# nfc-epd-sensors.net
KiCad netlist of a schematic drawn in Altium Designer
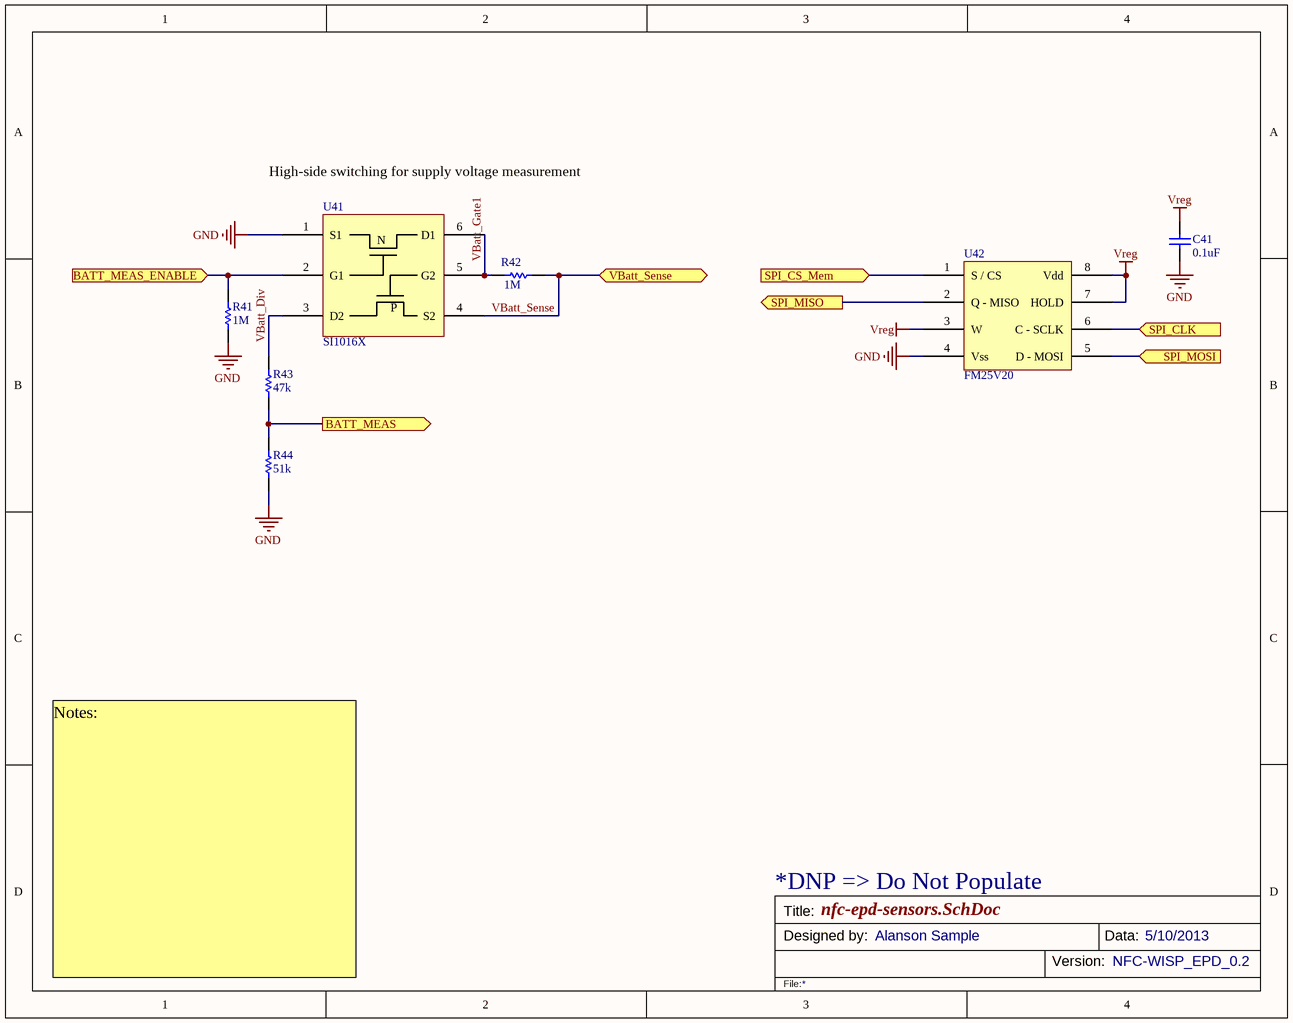
[diagram p0: nfc-epd-sensors.SchDoc]

(export (version "E")
  (design (tool "Eeschema 10.0.6"))
  (components
    (comp (ref "C41")
      (value "0.1uF")
      (footprint "0603")
      (description "Ceramic Capacitor (Surface Mount)")
      (fields (field (name "MANUFACTURER") "Generic Ceramic Chip Cap (TBD)") (field (name "Comment") "Cap"))
      (libsource (lib "WISP_AD10") (part "Cap"))
    )
    (comp (ref "R41")
      (value "1M")
      (footprint "0603")
      (description "Chip Resistor (Surface Mount)")
      (fields (field (name "MANUFACTURER") "Generic Chip Res (TBD)") (field (name "Comment") "Res"))
      (libsource (lib "WISP_AD10") (part "Res"))
    )
    (comp (ref "R42")
      (value "1M")
      (footprint "0603")
      (description "Chip Resistor (Surface Mount)")
      (fields (field (name "MANUFACTURER") "Generic Chip Res (TBD)") (field (name "Comment") "Res"))
      (libsource (lib "WISP_AD10") (part "Res"))
    )
    (comp (ref "R43")
      (value "47k")
      (footprint "0603")
      (description "Chip Resistor (Surface Mount)")
      (fields (field (name "MANUFACTURER") "Generic Chip Res (TBD)") (field (name "Comment") "Res"))
      (libsource (lib "WISP_AD10") (part "Res"))
    )
    (comp (ref "R44")
      (value "51k")
      (footprint "0603")
      (description "Chip Resistor (Surface Mount)")
      (fields (field (name "MANUFACTURER") "Generic Chip Res (TBD)") (field (name "Comment") "Res"))
      (libsource (lib "WISP_AD10") (part "Res"))
    )
    (comp (ref "U41")
      (value "SI1016X")
      (footprint "SC-89-6 Vishay")
      (description "NMOS and PMOS array")
      (fields
        (field (name "MANUFACTURER") "Vishay Siliconix")
        (field (name "MANUFACTURER PART NUMBER") "SI1016X-T1-GE3")
      )
      (libsource (lib "WISP_AD10") (part "SI1016X"))
    )
    (comp (ref "U42")
      (value "FM25V20")
      (footprint "TDFN-8")
      (description "2 Mbit FRAM SPI")
      (fields
        (field (name "DIGI-KEY PART NUMBER") "428-3214-ND")
        (field (name "MANUFACTURER") "Cypress Semiconductor Corp")
      )
      (libsource (lib "WISP_AD10") (part "FM25V20"))
    )
  )
  (nets
    (net (code "1") (name "/BATT_MEAS") (class "Default")
      (node (ref "R43") (pin "1") (pinfunction "1_1") (pintype "passive"))
      (node (ref "R44") (pin "2") (pinfunction "2_2") (pintype "passive"))
    )
    (net (code "2") (name "/BATT_MEAS_ENABLE") (class "Default")
      (node (ref "R41") (pin "2") (pinfunction "2_2") (pintype "passive"))
      (node (ref "U41") (pin "2") (pinfunction "G1_2") (pintype "passive"))
    )
    (net (code "3") (name "/SPI_CLK") (class "Default")
      (node (ref "U42") (pin "6") (pinfunction "C_-_SCLK_6") (pintype "passive"))
    )
    (net (code "4") (name "/SPI_CS_Mem") (class "Default")
      (node (ref "U42") (pin "1") (pinfunction "S_/_CS_1") (pintype "passive"))
    )
    (net (code "5") (name "/SPI_MISO") (class "Default")
      (node (ref "U42") (pin "2") (pinfunction "Q_-_MISO_2") (pintype "passive"))
    )
    (net (code "6") (name "/SPI_MOSI") (class "Default")
      (node (ref "U42") (pin "5") (pinfunction "D_-_MOSI_5") (pintype "passive"))
    )
    (net (code "7") (name "/VBatt_Div") (class "Default")
      (node (ref "R43") (pin "2") (pinfunction "2_2") (pintype "passive"))
      (node (ref "U41") (pin "3") (pinfunction "D2_3") (pintype "passive"))
    )
    (net (code "8") (name "/VBatt_Gate1") (class "Default")
      (node (ref "R42") (pin "2") (pinfunction "2_2") (pintype "passive"))
      (node (ref "U41") (pin "5") (pinfunction "G2_5") (pintype "passive"))
      (node (ref "U41") (pin "6") (pinfunction "D1_6") (pintype "passive"))
    )
    (net (code "9") (name "/VBatt_Sense") (class "Default")
      (node (ref "R42") (pin "1") (pinfunction "1_1") (pintype "passive"))
      (node (ref "U41") (pin "4") (pinfunction "S2_4") (pintype "passive"))
    )
    (net (code "10") (name "GND") (class "Default")
      (node (ref "C41") (pin "1") (pinfunction "1_1") (pintype "passive"))
      (node (ref "R41") (pin "1") (pinfunction "1_1") (pintype "passive"))
      (node (ref "R44") (pin "1") (pinfunction "1_1") (pintype "passive"))
      (node (ref "U41") (pin "1") (pinfunction "S1_1") (pintype "passive"))
      (node (ref "U42") (pin "4") (pinfunction "Vss_4") (pintype "passive"))
    )
    (net (code "11") (name "Vreg") (class "Default")
      (node (ref "C41") (pin "2") (pinfunction "2_2") (pintype "passive"))
      (node (ref "U42") (pin "3") (pinfunction "W_3") (pintype "passive"))
      (node (ref "U42") (pin "7") (pinfunction "HOLD_7") (pintype "passive"))
      (node (ref "U42") (pin "8") (pinfunction "Vdd_8") (pintype "passive"))
    )
  )
)
